# MS-FlipFlop.net
KiCad netlist of a schematic drawn in EAGLE
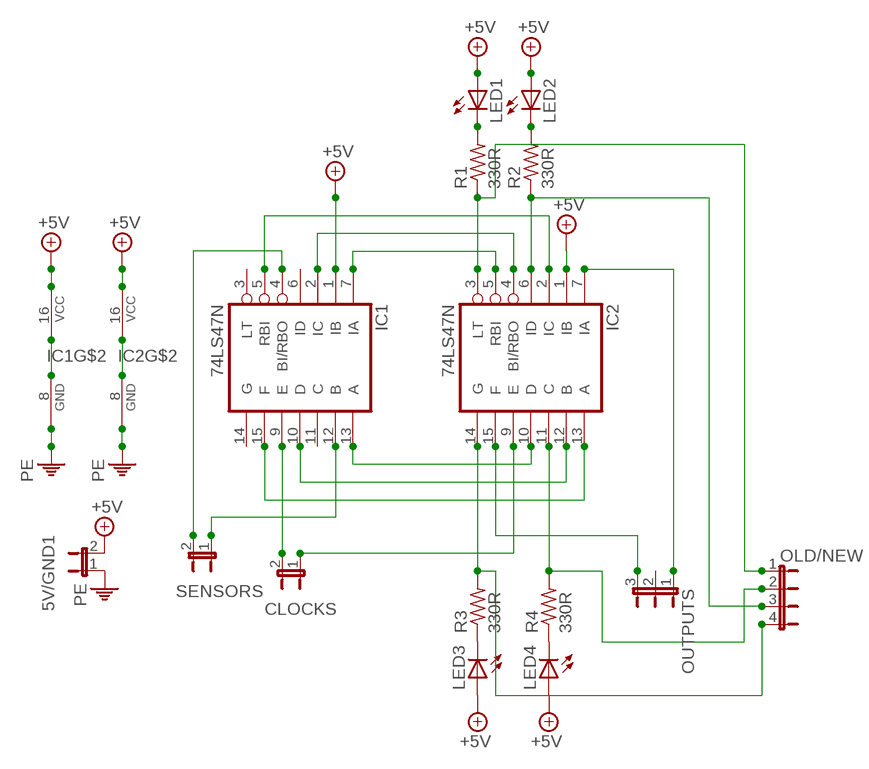
[diagram p0: schematic, sheet 1]

(export (version "E")
  (design (tool "Eeschema 10.0.6"))
  (components
    (comp (ref "5V/GND1")
      (value "JP1E")
      (footprint "eagle-import:JP1")
      (libsource (lib "eagle-import") (part "JP1E"))
    )
    (comp (ref "CLOCKS")
      (value "JP1E")
      (footprint "eagle-import:JP1")
      (libsource (lib "eagle-import") (part "JP1E"))
    )
    (comp (ref "IC1")
      (value "74LS47N")
      (footprint "eagle-import:DIL16")
      (libsource (lib "eagle-import") (part "7447NLS"))
    )
    (comp (ref "IC2")
      (value "74LS47N")
      (footprint "eagle-import:DIL16")
      (libsource (lib "eagle-import") (part "7447NLS"))
    )
    (comp (ref "LED1")
      (value "LED5MM")
      (footprint "eagle-import:LED5MM")
      (libsource (lib "eagle-import") (part "LED5MM"))
    )
    (comp (ref "LED2")
      (value "LED5MM")
      (footprint "eagle-import:LED5MM")
      (libsource (lib "eagle-import") (part "LED5MM"))
    )
    (comp (ref "LED3")
      (value "LED5MM")
      (footprint "eagle-import:LED5MM")
      (libsource (lib "eagle-import") (part "LED5MM"))
    )
    (comp (ref "LED4")
      (value "LED5MM")
      (footprint "eagle-import:LED5MM")
      (libsource (lib "eagle-import") (part "LED5MM"))
    )
    (comp (ref "OLD/NEW")
      (value "JP4E")
      (footprint "eagle-import:JP4")
      (libsource (lib "eagle-import") (part "JP4E"))
    )
    (comp (ref "OUTPUTS")
      (value "JP2E")
      (footprint "eagle-import:JP2")
      (libsource (lib "eagle-import") (part "JP2E"))
    )
    (comp (ref "R1")
      (value "330R")
      (footprint "eagle-import:0207_10")
      (libsource (lib "eagle-import") (part "R-US_0207/10"))
    )
    (comp (ref "R2")
      (value "330R")
      (footprint "eagle-import:0207_10")
      (libsource (lib "eagle-import") (part "R-US_0207/10"))
    )
    (comp (ref "R3")
      (value "330R")
      (footprint "eagle-import:0207_10")
      (libsource (lib "eagle-import") (part "R-US_0207/10"))
    )
    (comp (ref "R4")
      (value "330R")
      (footprint "eagle-import:0207_10")
      (libsource (lib "eagle-import") (part "R-US_0207/10"))
    )
    (comp (ref "SENSORS")
      (value "JP1E")
      (footprint "eagle-import:JP1")
      (libsource (lib "eagle-import") (part "JP1E"))
    )
  )
  (nets
    (net (code "1") (name "+5V") (class "Default")
      (node (ref "5V/GND1") (pin "2") (pinfunction "2_2") (pintype "passive"))
      (node (ref "IC1") (pin "1") (pinfunction "IB_1") (pintype "input"))
      (node (ref "IC1") (pin "16") (pinfunction "VCC_16") (pintype "power_in"))
      (node (ref "IC2") (pin "1") (pinfunction "IB_1") (pintype "input"))
      (node (ref "IC2") (pin "16") (pinfunction "VCC_16") (pintype "power_in"))
      (node (ref "LED1") (pin "A") (pinfunction "A_A") (pintype "passive"))
      (node (ref "LED2") (pin "A") (pinfunction "A_A") (pintype "passive"))
      (node (ref "LED3") (pin "A") (pinfunction "A_A") (pintype "passive"))
      (node (ref "LED4") (pin "A") (pinfunction "A_A") (pintype "passive"))
    )
    (net (code "2") (name "Net-(IC1A-A)") (class "Default")
      (node (ref "IC1") (pin "13") (pinfunction "A_13") (pintype "output"))
      (node (ref "IC2") (pin "10") (pinfunction "D_10") (pintype "output"))
    )
    (net (code "3") (name "Net-(IC1A-B)") (class "Default")
      (node (ref "IC1") (pin "12") (pinfunction "B_12") (pintype "output"))
      (node (ref "SENSORS") (pin "1") (pinfunction "1_1") (pintype "passive"))
    )
    (net (code "4") (name "Net-(IC1A-BI{slash}RBO)") (class "Default")
      (node (ref "IC1") (pin "4") (pinfunction "BI/RBO_4") (pintype "input"))
      (node (ref "SENSORS") (pin "2") (pinfunction "2_2") (pintype "passive"))
    )
    (net (code "5") (name "Net-(IC1A-D)") (class "Default")
      (node (ref "IC1") (pin "10") (pinfunction "D_10") (pintype "output"))
      (node (ref "IC2") (pin "12") (pinfunction "B_12") (pintype "output"))
    )
    (net (code "6") (name "Net-(IC1A-E)") (class "Default")
      (node (ref "CLOCKS") (pin "2") (pinfunction "2_2") (pintype "passive"))
      (node (ref "IC1") (pin "9") (pinfunction "E_9") (pintype "output"))
    )
    (net (code "7") (name "Net-(IC1A-F)") (class "Default")
      (node (ref "IC1") (pin "15") (pinfunction "F_15") (pintype "output"))
      (node (ref "IC2") (pin "13") (pinfunction "A_13") (pintype "output"))
    )
    (net (code "8") (name "Net-(IC1A-IA)") (class "Default")
      (node (ref "IC1") (pin "7") (pinfunction "IA_7") (pintype "input"))
      (node (ref "IC2") (pin "5") (pinfunction "RBI_5") (pintype "input"))
    )
    (net (code "9") (name "Net-(IC1A-IC)") (class "Default")
      (node (ref "IC1") (pin "2") (pinfunction "IC_2") (pintype "input"))
      (node (ref "IC2") (pin "4") (pinfunction "BI/RBO_4") (pintype "input"))
    )
    (net (code "10") (name "Net-(IC1A-RBI)") (class "Default")
      (node (ref "IC1") (pin "5") (pinfunction "RBI_5") (pintype "input"))
      (node (ref "IC2") (pin "2") (pinfunction "IC_2") (pintype "input"))
    )
    (net (code "11") (name "Net-(IC2A-C)") (class "Default")
      (node (ref "IC2") (pin "11") (pinfunction "C_11") (pintype "output"))
      (node (ref "OLD/NEW") (pin "2") (pinfunction "2_2") (pintype "passive"))
      (node (ref "R4") (pin "2") (pinfunction "2_2") (pintype "passive"))
    )
    (net (code "12") (name "Net-(IC2A-E)") (class "Default")
      (node (ref "CLOCKS") (pin "1") (pinfunction "1_1") (pintype "passive"))
      (node (ref "IC2") (pin "9") (pinfunction "E_9") (pintype "output"))
    )
    (net (code "13") (name "Net-(IC2A-F)") (class "Default")
      (node (ref "IC2") (pin "15") (pinfunction "F_15") (pintype "output"))
      (node (ref "OUTPUTS") (pin "3") (pinfunction "3_3") (pintype "passive"))
    )
    (net (code "14") (name "Net-(IC2A-G)") (class "Default")
      (node (ref "IC2") (pin "14") (pinfunction "G_14") (pintype "output"))
      (node (ref "OLD/NEW") (pin "4") (pinfunction "4_4") (pintype "passive"))
      (node (ref "R3") (pin "2") (pinfunction "2_2") (pintype "passive"))
    )
    (net (code "15") (name "Net-(IC2A-IA)") (class "Default")
      (node (ref "IC2") (pin "7") (pinfunction "IA_7") (pintype "input"))
      (node (ref "OUTPUTS") (pin "1") (pinfunction "1_1") (pintype "passive"))
    )
    (net (code "16") (name "Net-(IC2A-ID)") (class "Default")
      (node (ref "IC2") (pin "6") (pinfunction "ID_6") (pintype "input"))
      (node (ref "OLD/NEW") (pin "3") (pinfunction "3_3") (pintype "passive"))
      (node (ref "R2") (pin "1") (pinfunction "1_1") (pintype "passive"))
    )
    (net (code "17") (name "Net-(IC2A-LT)") (class "Default")
      (node (ref "IC2") (pin "3") (pinfunction "LT_3") (pintype "input"))
      (node (ref "OLD/NEW") (pin "1") (pinfunction "1_1") (pintype "passive"))
      (node (ref "R1") (pin "1") (pinfunction "1_1") (pintype "passive"))
    )
    (net (code "18") (name "Net-(LED1-C)") (class "Default")
      (node (ref "LED1") (pin "K") (pinfunction "C_K") (pintype "passive"))
      (node (ref "R1") (pin "2") (pinfunction "2_2") (pintype "passive"))
    )
    (net (code "19") (name "Net-(LED2-C)") (class "Default")
      (node (ref "LED2") (pin "K") (pinfunction "C_K") (pintype "passive"))
      (node (ref "R2") (pin "2") (pinfunction "2_2") (pintype "passive"))
    )
    (net (code "20") (name "Net-(LED3-C)") (class "Default")
      (node (ref "LED3") (pin "K") (pinfunction "C_K") (pintype "passive"))
      (node (ref "R3") (pin "1") (pinfunction "1_1") (pintype "passive"))
    )
    (net (code "21") (name "Net-(LED4-C)") (class "Default")
      (node (ref "LED4") (pin "K") (pinfunction "C_K") (pintype "passive"))
      (node (ref "R4") (pin "1") (pinfunction "1_1") (pintype "passive"))
    )
    (net (code "22") (name "PE") (class "Default")
      (node (ref "5V/GND1") (pin "1") (pinfunction "1_1") (pintype "passive"))
      (node (ref "IC1") (pin "8") (pinfunction "GND_8") (pintype "power_in"))
      (node (ref "IC2") (pin "8") (pinfunction "GND_8") (pintype "power_in"))
    )
    (net (code "23") (name "unconnected-(IC1A-C-Pad11)") (class "Default")
      (node (ref "IC1") (pin "11") (pinfunction "C_11") (pintype "output"))
    )
    (net (code "24") (name "unconnected-(IC1A-G-Pad14)") (class "Default")
      (node (ref "IC1") (pin "14") (pinfunction "G_14") (pintype "output"))
    )
    (net (code "25") (name "unconnected-(IC1A-ID-Pad6)") (class "Default")
      (node (ref "IC1") (pin "6") (pinfunction "ID_6") (pintype "input"))
    )
    (net (code "26") (name "unconnected-(IC1A-LT-Pad3)") (class "Default")
      (node (ref "IC1") (pin "3") (pinfunction "LT_3") (pintype "input"))
    )
    (net (code "27") (name "unconnected-(OUTPUTS-Pad2)") (class "Default")
      (node (ref "OUTPUTS") (pin "2") (pinfunction "2_2") (pintype "passive"))
    )
  )
)
